# machnguonxung.net
KiCad netlist of a schematic drawn in Altium Designer
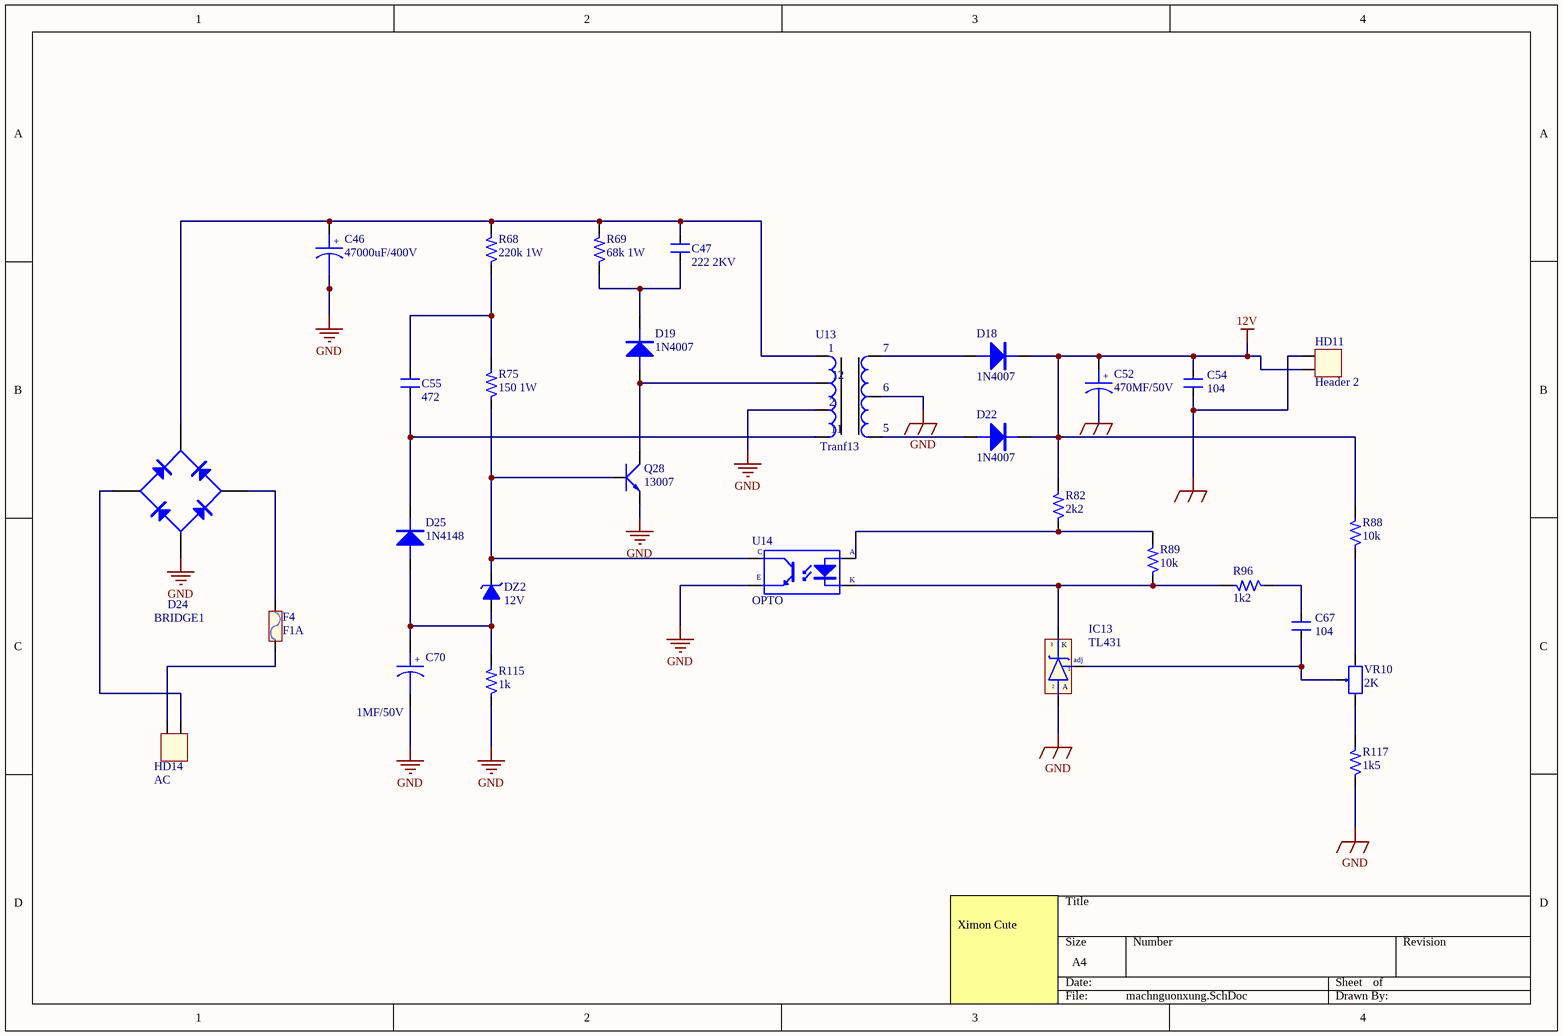
[diagram p0: machnguonxung.SchDoc]

(export (version "E")
  (design (tool "Eeschema 10.0.6"))
  (components
    (comp (ref "C46")
      (value "47000uF/400V")
      (footprint "CAP10UF")
      (description "Capacitor")
      (libsource (lib "Cty1") (part "CAPACITOR POL"))
    )
    (comp (ref "C47")
      (value "222 2KV")
      (footprint "SM-0805")
      (description "Cap SMD")
      (libsource (lib "VioletofSun") (part "CM"))
    )
    (comp (ref "C52")
      (value "470MF/50V")
      (footprint "CAP10UF")
      (description "Capacitor")
      (libsource (lib "Cty1") (part "CAPACITOR POL"))
    )
    (comp (ref "C54")
      (value "104")
      (footprint "SM-0805")
      (description "Cap SMD")
      (libsource (lib "VioletofSun") (part "CM"))
    )
    (comp (ref "C55")
      (value "472")
      (footprint "SM-0805")
      (description "Cap SMD")
      (libsource (lib "VioletofSun") (part "CM"))
    )
    (comp (ref "C67")
      (value "104")
      (footprint "SM-0805")
      (description "Cap SMD")
      (libsource (lib "VioletofSun") (part "CM"))
    )
    (comp (ref "C70")
      (value "CAPACI")
      (footprint "CAP10UF")
      (description "Capacitor")
      (libsource (lib "Cty1") (part "CAPACITOR POL"))
    )
    (comp (ref "D18")
      (value "1N4007")
      (footprint "diode")
      (description "Diode")
      (libsource (lib "Cty1") (part "DIODE"))
    )
    (comp (ref "D19")
      (value "1N4007")
      (footprint "diode")
      (description "Diode")
      (libsource (lib "Cty1") (part "DIODE"))
    )
    (comp (ref "D22")
      (value "1N4007")
      (footprint "diode")
      (description "Diode")
      (libsource (lib "Cty1") (part "DIODE"))
    )
    (comp (ref "D24")
      (value "BRIDGE1")
      (footprint "BRIDGE_DAN")
      (description "Diode Bridge")
      (libsource (lib "Cty1") (part "BRIDGE1"))
    )
    (comp (ref "D25")
      (value "1N4148")
      (footprint "diode")
      (description "Diode")
      (libsource (lib "Cty1") (part "DIODE"))
    )
    (comp (ref "DZ2")
      (value "12V")
      (footprint "D1A")
      (description "Diode  Zener")
      (libsource (lib "Cty1") (part "Diode Zener"))
    )
    (comp (ref "F4")
      (value "F1A")
      (footprint "Fuse")
      (description "Fuse")
      (fields (field (name "DESIGNED BY") "VanDungEvn"))
      (libsource (lib "syhaunguyen") (part "Fuse"))
    )
    (comp (ref "HD11")
      (value "Header 2")
      (footprint "HED2")
      (description "Header 2 (Green)")
      (libsource (lib "") (part "Hed2_1"))
    )
    (comp (ref "HD14")
      (value "AC")
      (footprint "HED2")
      (description "Header 2 (Green)")
      (libsource (lib "syhaunguyen") (part "Hed2"))
    )
    (comp (ref "IC13")
      (value "TL431")
      (footprint "qto-92")
      (description "Programmable Shunt Regulator")
      (libsource (lib "SCH_Lib_Devzone") (part "TL431"))
    )
    (comp (ref "Q28")
      (value "13007")
      (footprint "QTO-220")
      (description "P 1W, BCE")
      (libsource (lib "Cty1") (part "NPN_BCE"))
    )
    (comp (ref "R68")
      (value "220k 1W")
      (footprint "R1/6W")
      (description "Resistor 1/4W")
      (libsource (lib "Cty1") (part "Res"))
    )
    (comp (ref "R69")
      (value "68k 1W")
      (footprint "R1/6W")
      (description "Resistor 1/4W")
      (libsource (lib "Cty1") (part "Res"))
    )
    (comp (ref "R75")
      (value "150 1W")
      (footprint "R1/6W")
      (description "Resistor 1/4W")
      (libsource (lib "Cty1") (part "Res"))
    )
    (comp (ref "R82")
      (value "2k2")
      (footprint "R1/6W")
      (description "Resistor 1/4W")
      (libsource (lib "Cty1") (part "Res"))
    )
    (comp (ref "R88")
      (value "10k")
      (footprint "R1/6W")
      (description "Resistor 1/4W")
      (libsource (lib "Cty1") (part "Res"))
    )
    (comp (ref "R89")
      (value "10k")
      (footprint "R1/6W")
      (description "Resistor 1/4W")
      (libsource (lib "Cty1") (part "Res"))
    )
    (comp (ref "R96")
      (value "1k2")
      (footprint "R1/6W")
      (description "Resistor 1/4W")
      (libsource (lib "Cty1") (part "Res"))
    )
    (comp (ref "R115")
      (value "1k")
      (footprint "R1/6W")
      (description "Resistor 1/4W")
      (libsource (lib "Cty1") (part "Res"))
    )
    (comp (ref "R117")
      (value "1k5")
      (footprint "R1/6W")
      (description "Resistor 1/4W")
      (libsource (lib "Cty1") (part "Res"))
    )
    (comp (ref "U13")
      (value "Tranf13")
      (footprint "BAX_EE32")
      (description "Tranformer")
      (libsource (lib "SCH_Lib_Devzone") (part "BAX_EE32"))
    )
    (comp (ref "U14")
      (value "OPTO")
      (footprint "OPTO_U")
      (description "Single Opto")
      (libsource (lib "SCH_Lib_Devzone") (part "OPTO_U"))
    )
    (comp (ref "VR10")
      (value "2K")
      (footprint "VioletofSun:VR")
      (description "Var Resistor")
      (libsource (lib "VioletofSun") (part "VR"))
    )
  )
  (nets
    (net (code "1") (name "12V") (class "Default")
      (node (ref "C52") (pin "1") (pinfunction "1_1") (pintype "passive"))
      (node (ref "C54") (pin "2") (pinfunction "2_2") (pintype "passive"))
      (node (ref "D18") (pin "2") (pinfunction "2_2") (pintype "passive"))
      (node (ref "D22") (pin "2") (pinfunction "2_2") (pintype "passive"))
      (node (ref "HD11") (pin "2") (pinfunction "2_2") (pintype "passive"))
      (node (ref "R82") (pin "2") (pinfunction "2_2") (pintype "passive"))
      (node (ref "R88") (pin "2") (pinfunction "2_2") (pintype "passive"))
    )
    (net (code "2") (name "GND") (class "Default")
      (node (ref "C46") (pin "2") (pinfunction "2_2") (pintype "passive"))
      (node (ref "C52") (pin "2") (pinfunction "2_2") (pintype "passive"))
      (node (ref "C54") (pin "1") (pinfunction "1_1") (pintype "passive"))
      (node (ref "C70") (pin "2") (pinfunction "2_2") (pintype "passive"))
      (node (ref "D24") (pin "4") (pinfunction "V-_4") (pintype "passive"))
      (node (ref "HD11") (pin "1") (pinfunction "1_1") (pintype "passive"))
      (node (ref "IC13") (pin "2") (pinfunction "A_2") (pintype "passive"))
      (node (ref "Q28") (pin "3") (pinfunction "E_3") (pintype "passive"))
      (node (ref "R115") (pin "1") (pinfunction "1_1") (pintype "passive"))
      (node (ref "R117") (pin "1") (pinfunction "1_1") (pintype "passive"))
      (node (ref "U13") (pin "10") (pinfunction "10_10") (pintype "passive"))
      (node (ref "U13") (pin "3") (pinfunction "3_3") (pintype "passive"))
      (node (ref "U14") (pin "E") (pinfunction "E_E") (pintype "passive"))
    )
    (net (code "3") (name "Net-(C47-Pad1)") (class "Default")
      (node (ref "C47") (pin "1") (pinfunction "1_1") (pintype "passive"))
      (node (ref "D19") (pin "2") (pinfunction "2_2") (pintype "passive"))
      (node (ref "R69") (pin "1") (pinfunction "1_1") (pintype "passive"))
    )
    (net (code "4") (name "Net-(C55-Pad1)") (class "Default")
      (node (ref "C55") (pin "1") (pinfunction "1_1") (pintype "passive"))
      (node (ref "D25") (pin "2") (pinfunction "2_2") (pintype "passive"))
      (node (ref "U13") (pin "9") (pinfunction "9_9") (pintype "passive"))
    )
    (net (code "5") (name "Net-(C55-Pad2)") (class "Default")
      (node (ref "C55") (pin "2") (pinfunction "2_2") (pintype "passive"))
      (node (ref "R68") (pin "1") (pinfunction "1_1") (pintype "passive"))
      (node (ref "R75") (pin "2") (pinfunction "2_2") (pintype "passive"))
    )
    (net (code "6") (name "Net-(C67-Pad2)") (class "Default")
      (node (ref "C67") (pin "2") (pinfunction "2_2") (pintype "passive"))
      (node (ref "R96") (pin "1") (pinfunction "1_1") (pintype "passive"))
    )
    (net (code "7") (name "Net-(D18-Pad1)") (class "Default")
      (node (ref "D18") (pin "1") (pinfunction "1_1") (pintype "passive"))
      (node (ref "U13") (pin "1") (pinfunction "1_1") (pintype "passive"))
    )
    (net (code "8") (name "Net-(D22-Pad1)") (class "Default")
      (node (ref "D22") (pin "1") (pinfunction "1_1") (pintype "passive"))
      (node (ref "U13") (pin "6") (pinfunction "6_6") (pintype "passive"))
    )
    (net (code "9") (name "Net-(D24-AC-Pad2)") (class "Default")
      (node (ref "D24") (pin "2") (pinfunction "AC_2") (pintype "passive"))
      (node (ref "HD14") (pin "1") (pinfunction "1_1") (pintype "passive"))
    )
    (net (code "10") (name "Net-(D24-AC-Pad3)") (class "Default")
      (node (ref "D24") (pin "3") (pinfunction "AC_3") (pintype "passive"))
      (node (ref "F4") (pin "2") (pinfunction "2_2") (pintype "passive"))
    )
    (net (code "11") (name "Net-(D24-V+)") (class "Default")
      (node (ref "C46") (pin "1") (pinfunction "1_1") (pintype "passive"))
      (node (ref "C47") (pin "2") (pinfunction "2_2") (pintype "passive"))
      (node (ref "D24") (pin "1") (pinfunction "V+_1") (pintype "passive"))
      (node (ref "R68") (pin "2") (pinfunction "2_2") (pintype "passive"))
      (node (ref "R69") (pin "2") (pinfunction "2_2") (pintype "passive"))
      (node (ref "U13") (pin "12") (pinfunction "12_12") (pintype "passive"))
    )
    (net (code "12") (name "Net-(DZ2-A)") (class "Default")
      (node (ref "C70") (pin "1") (pinfunction "1_1") (pintype "passive"))
      (node (ref "D25") (pin "1") (pinfunction "1_1") (pintype "passive"))
      (node (ref "DZ2") (pin "1") (pinfunction "A_1") (pintype "passive"))
      (node (ref "R115") (pin "2") (pinfunction "2_2") (pintype "passive"))
    )
    (net (code "13") (name "Net-(DZ2-K)") (class "Default")
      (node (ref "DZ2") (pin "2") (pinfunction "K_2") (pintype "passive"))
      (node (ref "Q28") (pin "1") (pinfunction "B_1") (pintype "passive"))
      (node (ref "R75") (pin "1") (pinfunction "1_1") (pintype "passive"))
      (node (ref "U14") (pin "C") (pinfunction "C_C") (pintype "passive"))
    )
    (net (code "14") (name "Net-(F4-Pad1)") (class "Default")
      (node (ref "F4") (pin "1") (pinfunction "1_1") (pintype "passive"))
      (node (ref "HD14") (pin "2") (pinfunction "2_2") (pintype "passive"))
    )
    (net (code "15") (name "Net-(IC13-K)") (class "Default")
      (node (ref "IC13") (pin "3") (pinfunction "K_3") (pintype "passive"))
      (node (ref "R89") (pin "1") (pinfunction "1_1") (pintype "passive"))
      (node (ref "R96") (pin "2") (pinfunction "2_2") (pintype "passive"))
      (node (ref "U14") (pin "K") (pinfunction "K_K") (pintype "passive"))
    )
    (net (code "16") (name "Net-(IC13-adj)") (class "Default")
      (node (ref "C67") (pin "1") (pinfunction "1_1") (pintype "passive"))
      (node (ref "IC13") (pin "1") (pinfunction "adj_1") (pintype "passive"))
      (node (ref "VR10") (pin "2") (pinfunction "2_2") (pintype "passive"))
    )
    (net (code "17") (name "Net-(Q28-C)") (class "Default")
      (node (ref "D19") (pin "1") (pinfunction "1_1") (pintype "passive"))
      (node (ref "Q28") (pin "2") (pinfunction "C_2") (pintype "passive"))
      (node (ref "U13") (pin "11") (pinfunction "11_11") (pintype "passive"))
    )
    (net (code "18") (name "Net-(R82-Pad1)") (class "Default")
      (node (ref "R82") (pin "1") (pinfunction "1_1") (pintype "passive"))
      (node (ref "R89") (pin "2") (pinfunction "2_2") (pintype "passive"))
      (node (ref "U14") (pin "A") (pinfunction "A_A") (pintype "passive"))
    )
    (net (code "19") (name "Net-(R88-Pad1)") (class "Default")
      (node (ref "R88") (pin "1") (pinfunction "1_1") (pintype "passive"))
      (node (ref "VR10") (pin "3") (pinfunction "3_3") (pintype "passive"))
    )
    (net (code "20") (name "Net-(R117-Pad2)") (class "Default")
      (node (ref "R117") (pin "2") (pinfunction "2_2") (pintype "passive"))
      (node (ref "VR10") (pin "1") (pinfunction "1_1") (pintype "passive"))
    )
  )
)
